# 02_USB_MCU.net
KiCad netlist of a schematic drawn in Altium Designer
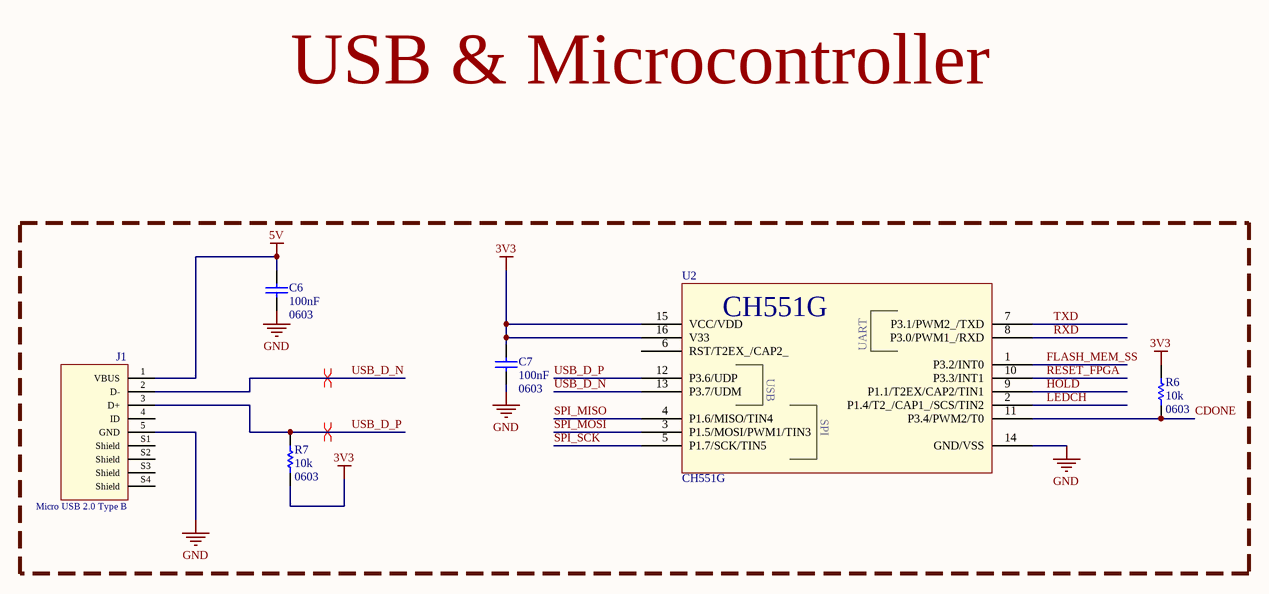
[diagram p0: 02_USB_MCU.SchDoc]

(export (version "E")
  (design (tool "Eeschema 10.0.6"))
  (components
    (comp (ref "C6")
      (value "100nF")
      (footprint "0603 CAP")
      (description "Capacitor")
      (fields (field (name "PACKAGE") "0603") (field (name "Comment") "Ceramic capacitor"))
      (libsource (lib "NodeFPGA") (part "Capacitor"))
    )
    (comp (ref "C7")
      (value "100nF")
      (footprint "0603 CAP")
      (description "Capacitor")
      (fields (field (name "PACKAGE") "0603") (field (name "Comment") "Ceramic capacitor"))
      (libsource (lib "NodeFPGA") (part "Capacitor"))
    )
    (comp (ref "J1")
      (value "Micro USB 2.0 Type B")
      (footprint "629105136821")
      (description "Micro USB 2.0 Type B Horizontal SMT 5 Contacts WR-COM")
      (fields (field (name "PART NUMBER") "629105136821") (field (name "PUBLISHER") "Wurth Elektronik"))
      (libsource (lib "NodeFPGA") (part "629105136821"))
    )
    (comp (ref "R6")
      (value "10k")
      (footprint "Resistencia 0603")
      (description "Resistor")
      (fields (field (name "PACKAGE") "0603"))
      (libsource (lib "NodeFPGA") (part "Resistor"))
    )
    (comp (ref "R7")
      (value "10k")
      (footprint "Resistencia 0603")
      (description "Resistor")
      (fields (field (name "PACKAGE") "0603"))
      (libsource (lib "NodeFPGA") (part "Resistor"))
    )
    (comp (ref "U2")
      (value "CH551G")
      (footprint "CH551")
      (description "Microcontroller wUSB support")
      (libsource (lib "NodeFPGA") (part "CH551G"))
    )
  )
  (nets
    (net (code "1") (name "/CDONE") (class "Default")
      (node (ref "R6") (pin "1") (pinfunction "1_1") (pintype "passive"))
      (node (ref "U2") (pin "11") (pinfunction "P3.4/PWM2/T0_11") (pintype "passive"))
    )
    (net (code "2") (name "/FLASH_MEM_SS") (class "Default")
      (node (ref "U2") (pin "1") (pinfunction "P3.2/INT0_1") (pintype "passive"))
    )
    (net (code "3") (name "/HOLD") (class "Default")
      (node (ref "U2") (pin "9") (pinfunction "P1.1/T2EX/CAP2/TIN1_9") (pintype "passive"))
    )
    (net (code "4") (name "/LEDCH") (class "Default")
      (node (ref "U2") (pin "2") (pinfunction "P1.4/T2_/CAP1_/SCS/TIN2_2") (pintype "passive"))
    )
    (net (code "5") (name "/RESET_FPGA") (class "Default")
      (node (ref "U2") (pin "10") (pinfunction "P3.3/INT1_10") (pintype "passive"))
    )
    (net (code "6") (name "/RXD") (class "Default")
      (node (ref "U2") (pin "8") (pinfunction "P3.0/PWM1_/RXD_8") (pintype "passive"))
    )
    (net (code "7") (name "/SPI_MISO") (class "Default")
      (node (ref "U2") (pin "4") (pinfunction "P1.6/MISO/TIN4_4") (pintype "passive"))
    )
    (net (code "8") (name "/SPI_MOSI") (class "Default")
      (node (ref "U2") (pin "3") (pinfunction "P1.5/MOSI/PWM1/TIN3_3") (pintype "passive"))
    )
    (net (code "9") (name "/SPI_SCK") (class "Default")
      (node (ref "U2") (pin "5") (pinfunction "P1.7/SCK/TIN5_5") (pintype "passive"))
    )
    (net (code "10") (name "/TXD") (class "Default")
      (node (ref "U2") (pin "7") (pinfunction "P3.1/PWM2_/TXD_7") (pintype "passive"))
    )
    (net (code "11") (name "/USB_D_N") (class "Default")
      (node (ref "J1") (pin "2") (pinfunction "D-_2") (pintype "passive"))
      (node (ref "U2") (pin "13") (pinfunction "P3.7/UDM_13") (pintype "passive"))
    )
    (net (code "12") (name "/USB_D_P") (class "Default")
      (node (ref "J1") (pin "3") (pinfunction "D+_3") (pintype "passive"))
      (node (ref "R7") (pin "1") (pinfunction "1_1") (pintype "passive"))
      (node (ref "U2") (pin "12") (pinfunction "P3.6/UDP_12") (pintype "passive"))
    )
    (net (code "13") (name "3V3") (class "Default")
      (node (ref "C7") (pin "1") (pinfunction "1_1") (pintype "passive"))
      (node (ref "R6") (pin "2") (pinfunction "2_2") (pintype "passive"))
      (node (ref "R7") (pin "2") (pinfunction "2_2") (pintype "passive"))
      (node (ref "U2") (pin "15") (pinfunction "VCC/VDD_15") (pintype "passive"))
      (node (ref "U2") (pin "16") (pinfunction "V33_16") (pintype "passive"))
    )
    (net (code "14") (name "5V") (class "Default")
      (node (ref "C6") (pin "1") (pinfunction "1_1") (pintype "passive"))
      (node (ref "J1") (pin "1") (pinfunction "VBUS_1") (pintype "passive"))
    )
    (net (code "15") (name "GND") (class "Default")
      (node (ref "C6") (pin "2") (pinfunction "2_2") (pintype "passive"))
      (node (ref "C7") (pin "2") (pinfunction "2_2") (pintype "passive"))
      (node (ref "J1") (pin "5") (pinfunction "GND_5") (pintype "passive"))
      (node (ref "U2") (pin "14") (pinfunction "GND/VSS_14") (pintype "passive"))
    )
    (net (code "16") (name "unconnected-(J1-ID-Pad4)") (class "Default")
      (node (ref "J1") (pin "4") (pinfunction "ID_4") (pintype "passive"))
    )
    (net (code "17") (name "unconnected-(J1-Shield-PadS1)") (class "Default")
      (node (ref "J1") (pin "S1") (pinfunction "Shield_S1") (pintype "passive"))
    )
    (net (code "18") (name "unconnected-(J1-Shield-PadS2)") (class "Default")
      (node (ref "J1") (pin "S2") (pinfunction "Shield_S2") (pintype "passive"))
    )
    (net (code "19") (name "unconnected-(J1-Shield-PadS3)") (class "Default")
      (node (ref "J1") (pin "S3") (pinfunction "Shield_S3") (pintype "passive"))
    )
    (net (code "20") (name "unconnected-(J1-Shield-PadS4)") (class "Default")
      (node (ref "J1") (pin "S4") (pinfunction "Shield_S4") (pintype "passive"))
    )
    (net (code "21") (name "unconnected-(U2-RST{slash}T2EX_{slash}CAP2_-Pad6)") (class "Default")
      (node (ref "U2") (pin "6") (pinfunction "RST/T2EX_/CAP2__6") (pintype "passive"))
    )
  )
)
